# POWER.net
KiCad netlist of a schematic drawn in Altium Designer
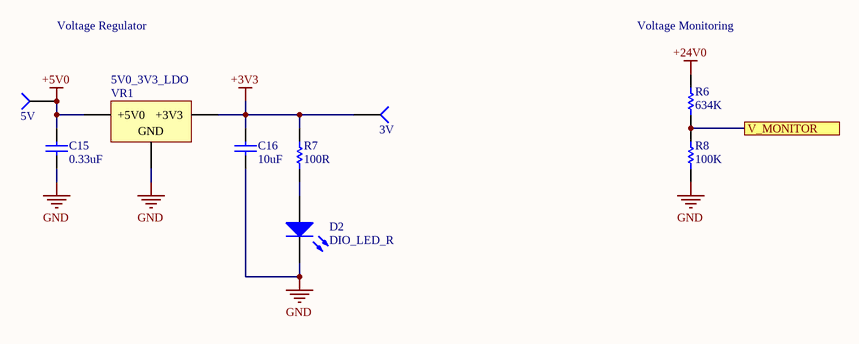
[diagram p0: POWER.SchDoc]

(export (version "E")
  (design (tool "Eeschema 10.0.6"))
  (components
    (comp (ref "2")
      (value "5V")
      (footprint "TESTPOINT")
      (libsource (lib "UWRT_Schematic_Library_2019") (part "TESTPOINT_SMD"))
    )
    (comp (ref "C15")
      (value "0.33uF")
      (footprint "CAPC0603(1608)55_N")
      (description "CAP CER 0.33UF 16V X7R 0603")
      (fields
        (field (name "PART NUMBER") "GRM188R71C334KA01D")
        (field (name "MANUFACTURER") "Murata Electronics North America")
      )
      (libsource (lib "UWRT_Schematic_Library_2019") (part "CAP_0.33uF_16V_0603"))
    )
    (comp (ref "C16")
      (value "10uF")
      (footprint "CAPC0603(1608)55_N")
      (description "CAP CER 10UF 10V X5R 0603")
      (fields (field (name "PART NUMBER") "CC0603MRX5R6BB106") (field (name "MANUFACTURER") "Yageo"))
      (libsource (lib "UWRT_Schematic_Library_2019") (part "CAP_10uF_0603"))
    )
    (comp (ref "D2")
      (value "DIO_LED_R")
      (footprint "LED_0805_LINE")
      (description "LED RED DIFFUSED 0805 SMD")
      (fields (field (name "PART NUMBER") "LS R976-NR-1") (field (name "MANUFACTURER") "OSRAM"))
      (libsource (lib "UWRT_Schematic_Library_2019") (part "DIO_LED_R"))
    )
    (comp (ref "R6")
      (value "634K")
      (footprint "RESC0603(1608)_N")
      (description "RES SMD 634K OHM 1% 1/10W 0603")
      (fields (field (name "MANUFACTURER") "Yageo") (field (name "TOLERANCE") "1%"))
      (libsource (lib "UWRT_Schematic_Library_2019") (part "RES_634K_0603"))
    )
    (comp (ref "R7")
      (value "100R")
      (footprint "RESC0603(1608)_N")
      (description "RES SMD 100 OHM 1% 1/10W 0603")
      (fields (field (name "MANUFACTURER") "Yageo") (field (name "TOLERANCE") "1%"))
      (libsource (lib "UWRT_Schematic_Library_2019") (part "RES_100R_0603"))
    )
    (comp (ref "R8")
      (value "100K")
      (footprint "RESC0603(1608)_N")
      (description "RES SMD 100K OHM 5% 1/10W 0603")
      (fields (field (name "MANUFACTURER") "Yageo") (field (name "TOLERANCE") "5%"))
      (libsource (lib "Safety") (part "RES_100K_0603"))
    )
    (comp (ref "TP6")
      (value "3V")
      (footprint "TESTPOINT")
      (libsource (lib "UWRT_Schematic_Library_2019") (part "TESTPOINT_SMD"))
    )
    (comp (ref "VR1")
      (value "5V0_3V3_LDO")
      (footprint "UWRT_Footprint_Library_2019:VOLTAGE_REGULATOR")
      (description "IC REG LINEAR 3.3V 1A DPAK")
      (fields (field (name "PART NUMBER") "NCP1117DT33T5G") (field (name "MANUFACTURER") "ON Semiconductor"))
      (libsource (lib "UWRT_Schematic_Library_2019") (part "5V0_3V3_LDO"))
    )
  )
  (nets
    (net (code "1") (name "+3V3") (class "Default")
      (node (ref "C16") (pin "2") (pinfunction "2_2") (pintype "passive"))
      (node (ref "R7") (pin "2") (pinfunction "2_2") (pintype "passive"))
      (node (ref "TP6") (pin "1") (pinfunction "=value_1") (pintype "passive"))
      (node (ref "VR1") (pin "4") (pinfunction "+3V3_4") (pintype "passive"))
    )
    (net (code "2") (name "+5V0") (class "Default")
      (node (ref "2") (pin "1") (pinfunction "=value_1") (pintype "passive"))
      (node (ref "C15") (pin "2") (pinfunction "2_2") (pintype "passive"))
      (node (ref "VR1") (pin "3") (pinfunction "+5V0_3") (pintype "passive"))
    )
    (net (code "3") (name "+24V0") (class "Default")
      (node (ref "R6") (pin "2") (pinfunction "2_2") (pintype "passive"))
    )
    (net (code "4") (name "/V_MONITOR") (class "Default")
      (node (ref "R6") (pin "1") (pinfunction "1_1") (pintype "passive"))
      (node (ref "R8") (pin "2") (pinfunction "2_2") (pintype "passive"))
    )
    (net (code "5") (name "GND") (class "Default")
      (node (ref "C15") (pin "1") (pinfunction "1_1") (pintype "passive"))
      (node (ref "C16") (pin "1") (pinfunction "1_1") (pintype "passive"))
      (node (ref "D2") (pin "2") (pinfunction "K_2") (pintype "passive"))
      (node (ref "R8") (pin "1") (pinfunction "1_1") (pintype "passive"))
      (node (ref "VR1") (pin "1") (pinfunction "GND_1") (pintype "passive"))
    )
    (net (code "6") (name "Net-(D2-A)") (class "Default")
      (node (ref "D2") (pin "1") (pinfunction "A_1") (pintype "passive"))
      (node (ref "R7") (pin "1") (pinfunction "1_1") (pintype "passive"))
    )
  )
)
